# v2_front_panel.net
KiCad netlist of a schematic drawn in EAGLE
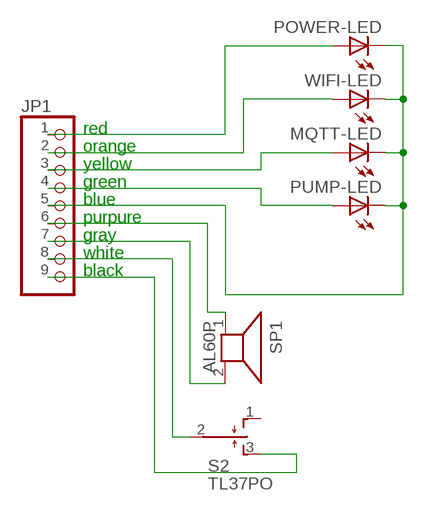
[diagram p0: schematic, sheet 1]

(export (version "E")
  (design (tool "Eeschema 10.0.6"))
  (components
    (comp (ref "JP1")
      (value "PINHD-1X9")
      (footprint "eagle-import:1X09")
      (libsource (lib "eagle-import") (part "PINHD-1X9"))
    )
    (comp (ref "MQTT-LED")
      (value "LED3MM")
      (footprint "eagle-import:LED3MM")
      (libsource (lib "eagle-import") (part "LED3MM"))
    )
    (comp (ref "POWER-LED")
      (value "LED3MM")
      (footprint "eagle-import:LED3MM")
      (libsource (lib "eagle-import") (part "LED3MM"))
    )
    (comp (ref "PUMP-LED")
      (value "LED3MM")
      (footprint "eagle-import:LED3MM")
      (libsource (lib "eagle-import") (part "LED3MM"))
    )
    (comp (ref "S2")
      (value "TL37PO")
      (footprint "eagle-import:TL3XPO")
      (libsource (lib "eagle-import") (part "TL37PO"))
    )
    (comp (ref "SP1")
      (value "AL60P")
      (footprint "eagle-import:AL60P")
      (libsource (lib "eagle-import") (part "AL60P"))
    )
    (comp (ref "WIFI-LED")
      (value "LED3MM")
      (footprint "eagle-import:LED3MM")
      (libsource (lib "eagle-import") (part "LED3MM"))
    )
  )
  (nets
    (net (code "1") (name "Net-(JP1-Pad1)") (class "Default")
      (node (ref "JP1") (pin "1") (pinfunction "1_1") (pintype "passive"))
      (node (ref "POWER-LED") (pin "A") (pinfunction "A_A") (pintype "passive"))
    )
    (net (code "2") (name "Net-(JP1-Pad2)") (class "Default")
      (node (ref "JP1") (pin "2") (pinfunction "2_2") (pintype "passive"))
      (node (ref "WIFI-LED") (pin "A") (pinfunction "A_A") (pintype "passive"))
    )
    (net (code "3") (name "Net-(JP1-Pad3)") (class "Default")
      (node (ref "JP1") (pin "3") (pinfunction "3_3") (pintype "passive"))
      (node (ref "MQTT-LED") (pin "A") (pinfunction "A_A") (pintype "passive"))
    )
    (net (code "4") (name "Net-(JP1-Pad4)") (class "Default")
      (node (ref "JP1") (pin "4") (pinfunction "4_4") (pintype "passive"))
      (node (ref "PUMP-LED") (pin "A") (pinfunction "A_A") (pintype "passive"))
    )
    (net (code "5") (name "Net-(JP1-Pad6)") (class "Default")
      (node (ref "JP1") (pin "6") (pinfunction "6_6") (pintype "passive"))
      (node (ref "SP1") (pin "1") (pinfunction "1_1") (pintype "passive"))
    )
    (net (code "6") (name "Net-(JP1-Pad7)") (class "Default")
      (node (ref "JP1") (pin "7") (pinfunction "7_7") (pintype "passive"))
      (node (ref "SP1") (pin "2") (pinfunction "2_2") (pintype "passive"))
    )
    (net (code "7") (name "Net-(MQTT-LED-C)") (class "Default")
      (node (ref "JP1") (pin "5") (pinfunction "5_5") (pintype "passive"))
      (node (ref "MQTT-LED") (pin "K") (pinfunction "C_K") (pintype "passive"))
      (node (ref "POWER-LED") (pin "K") (pinfunction "C_K") (pintype "passive"))
      (node (ref "PUMP-LED") (pin "K") (pinfunction "C_K") (pintype "passive"))
      (node (ref "WIFI-LED") (pin "K") (pinfunction "C_K") (pintype "passive"))
    )
    (net (code "8") (name "Net-(S2-P)") (class "Default")
      (node (ref "JP1") (pin "8") (pinfunction "8_8") (pintype "passive"))
      (node (ref "S2") (pin "2") (pinfunction "P_2") (pintype "passive"))
    )
    (net (code "9") (name "Net-(S2-S)") (class "Default")
      (node (ref "JP1") (pin "9") (pinfunction "9_9") (pintype "passive"))
      (node (ref "S2") (pin "3") (pinfunction "S_3") (pintype "passive"))
    )
    (net (code "10") (name "unconnected-(S2-O-Pad1)") (class "Default")
      (node (ref "S2") (pin "1") (pinfunction "O_1") (pintype "passive"))
    )
  )
)
